# MCU.net
KiCad netlist of a schematic drawn in Altium Designer
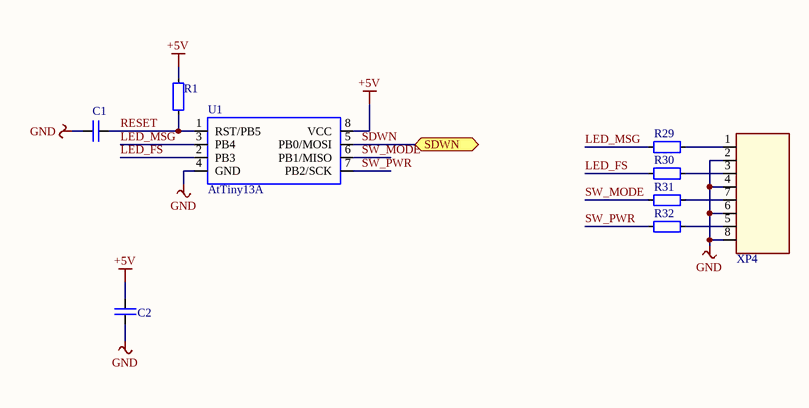
[diagram p0: MCU.SchDoc]

(export (version "E")
  (design (tool "Eeschema 10.0.6"))
  (components
    (comp (ref "C1")
      (value "~")
      (footprint "DISCRETE:SMD_0805")
      (description "None polar capacitor")
      (libsource (lib "DISCRETE") (part "C_NONE_POLAR"))
    )
    (comp (ref "C2")
      (value "~")
      (footprint "DISCRETE:SMD_0805")
      (description "None polar capacitor")
      (libsource (lib "DISCRETE") (part "C_NONE_POLAR"))
    )
    (comp (ref "R1")
      (value "~")
      (footprint "DISCRETE:SMD_0805")
      (description "Resistor")
      (libsource (lib "") (part "RES_1"))
    )
    (comp (ref "R29")
      (value "~")
      (footprint "DISCRETE:SMD_0805")
      (description "Resistor")
      (libsource (lib "DISCRETE") (part "RES"))
    )
    (comp (ref "R30")
      (value "~")
      (footprint "DISCRETE:SMD_0805")
      (description "Resistor")
      (libsource (lib "DISCRETE") (part "RES"))
    )
    (comp (ref "R31")
      (value "~")
      (footprint "DISCRETE:SMD_0805")
      (description "Resistor")
      (libsource (lib "DISCRETE") (part "RES"))
    )
    (comp (ref "R32")
      (value "~")
      (footprint "DISCRETE:SMD_0805")
      (description "Resistor")
      (libsource (lib "DISCRETE") (part "RES"))
    )
    (comp (ref "U1")
      (value "AtTiny13A")
      (footprint "ICs:SO8-150mil")
      (libsource (lib "ICs") (part "AtTiny13A"))
    )
    (comp (ref "XP4")
      (value "CON_8")
      (footprint "Connectors:HEAD-1/8/2.54")
      (libsource (lib "Connectors") (part "CON_8"))
    )
  )
  (nets
    (net (code "1") (name "+5V") (class "Default")
      (node (ref "C2") (pin "1") (pintype "passive"))
      (node (ref "R1") (pin "2") (pintype "passive"))
      (node (ref "U1") (pin "8") (pinfunction "VCC_8") (pintype "passive"))
    )
    (net (code "2") (name "/LED_FS") (class "Default")
      (node (ref "R30") (pin "2") (pintype "passive"))
      (node (ref "U1") (pin "2") (pinfunction "PB3_2") (pintype "passive"))
    )
    (net (code "3") (name "/LED_MSG") (class "Default")
      (node (ref "R29") (pin "2") (pintype "passive"))
      (node (ref "U1") (pin "3") (pinfunction "PB4_3") (pintype "passive"))
    )
    (net (code "4") (name "/RESET") (class "Default")
      (node (ref "C1") (pin "2") (pintype "passive"))
      (node (ref "R1") (pin "1") (pintype "passive"))
      (node (ref "U1") (pin "1") (pinfunction "RST/PB5_1") (pintype "passive"))
    )
    (net (code "5") (name "/SDWN") (class "Default")
      (node (ref "U1") (pin "5") (pinfunction "PB0/MOSI_5") (pintype "passive"))
    )
    (net (code "6") (name "/SW_MODE") (class "Default")
      (node (ref "R31") (pin "2") (pintype "passive"))
      (node (ref "U1") (pin "6") (pinfunction "PB1/MISO_6") (pintype "passive"))
    )
    (net (code "7") (name "/SW_PWR") (class "Default")
      (node (ref "R32") (pin "2") (pintype "passive"))
      (node (ref "U1") (pin "7") (pinfunction "PB2/SCK_7") (pintype "passive"))
    )
    (net (code "8") (name "GND") (class "Default")
      (node (ref "C1") (pin "1") (pintype "passive"))
      (node (ref "C2") (pin "2") (pintype "passive"))
      (node (ref "U1") (pin "4") (pinfunction "GND_4") (pintype "passive"))
      (node (ref "XP4") (pin "2") (pinfunction "2_2") (pintype "passive"))
      (node (ref "XP4") (pin "4") (pinfunction "4_4") (pintype "passive"))
      (node (ref "XP4") (pin "6") (pinfunction "6_6") (pintype "passive"))
      (node (ref "XP4") (pin "8") (pinfunction "8_8") (pintype "passive"))
    )
    (net (code "9") (name "Net-(R29-Pad1)") (class "Default")
      (node (ref "R29") (pin "1") (pintype "passive"))
      (node (ref "XP4") (pin "1") (pinfunction "1_1") (pintype "passive"))
    )
    (net (code "10") (name "Net-(R30-Pad1)") (class "Default")
      (node (ref "R30") (pin "1") (pintype "passive"))
      (node (ref "XP4") (pin "3") (pinfunction "3_3") (pintype "passive"))
    )
    (net (code "11") (name "Net-(R31-Pad1)") (class "Default")
      (node (ref "R31") (pin "1") (pintype "passive"))
      (node (ref "XP4") (pin "7") (pinfunction "7_7") (pintype "passive"))
    )
    (net (code "12") (name "Net-(R32-Pad1)") (class "Default")
      (node (ref "R32") (pin "1") (pintype "passive"))
      (node (ref "XP4") (pin "5") (pinfunction "5_5") (pintype "passive"))
    )
  )
)
